# v0_5_1.net
KiCad netlist of a schematic drawn in EAGLE
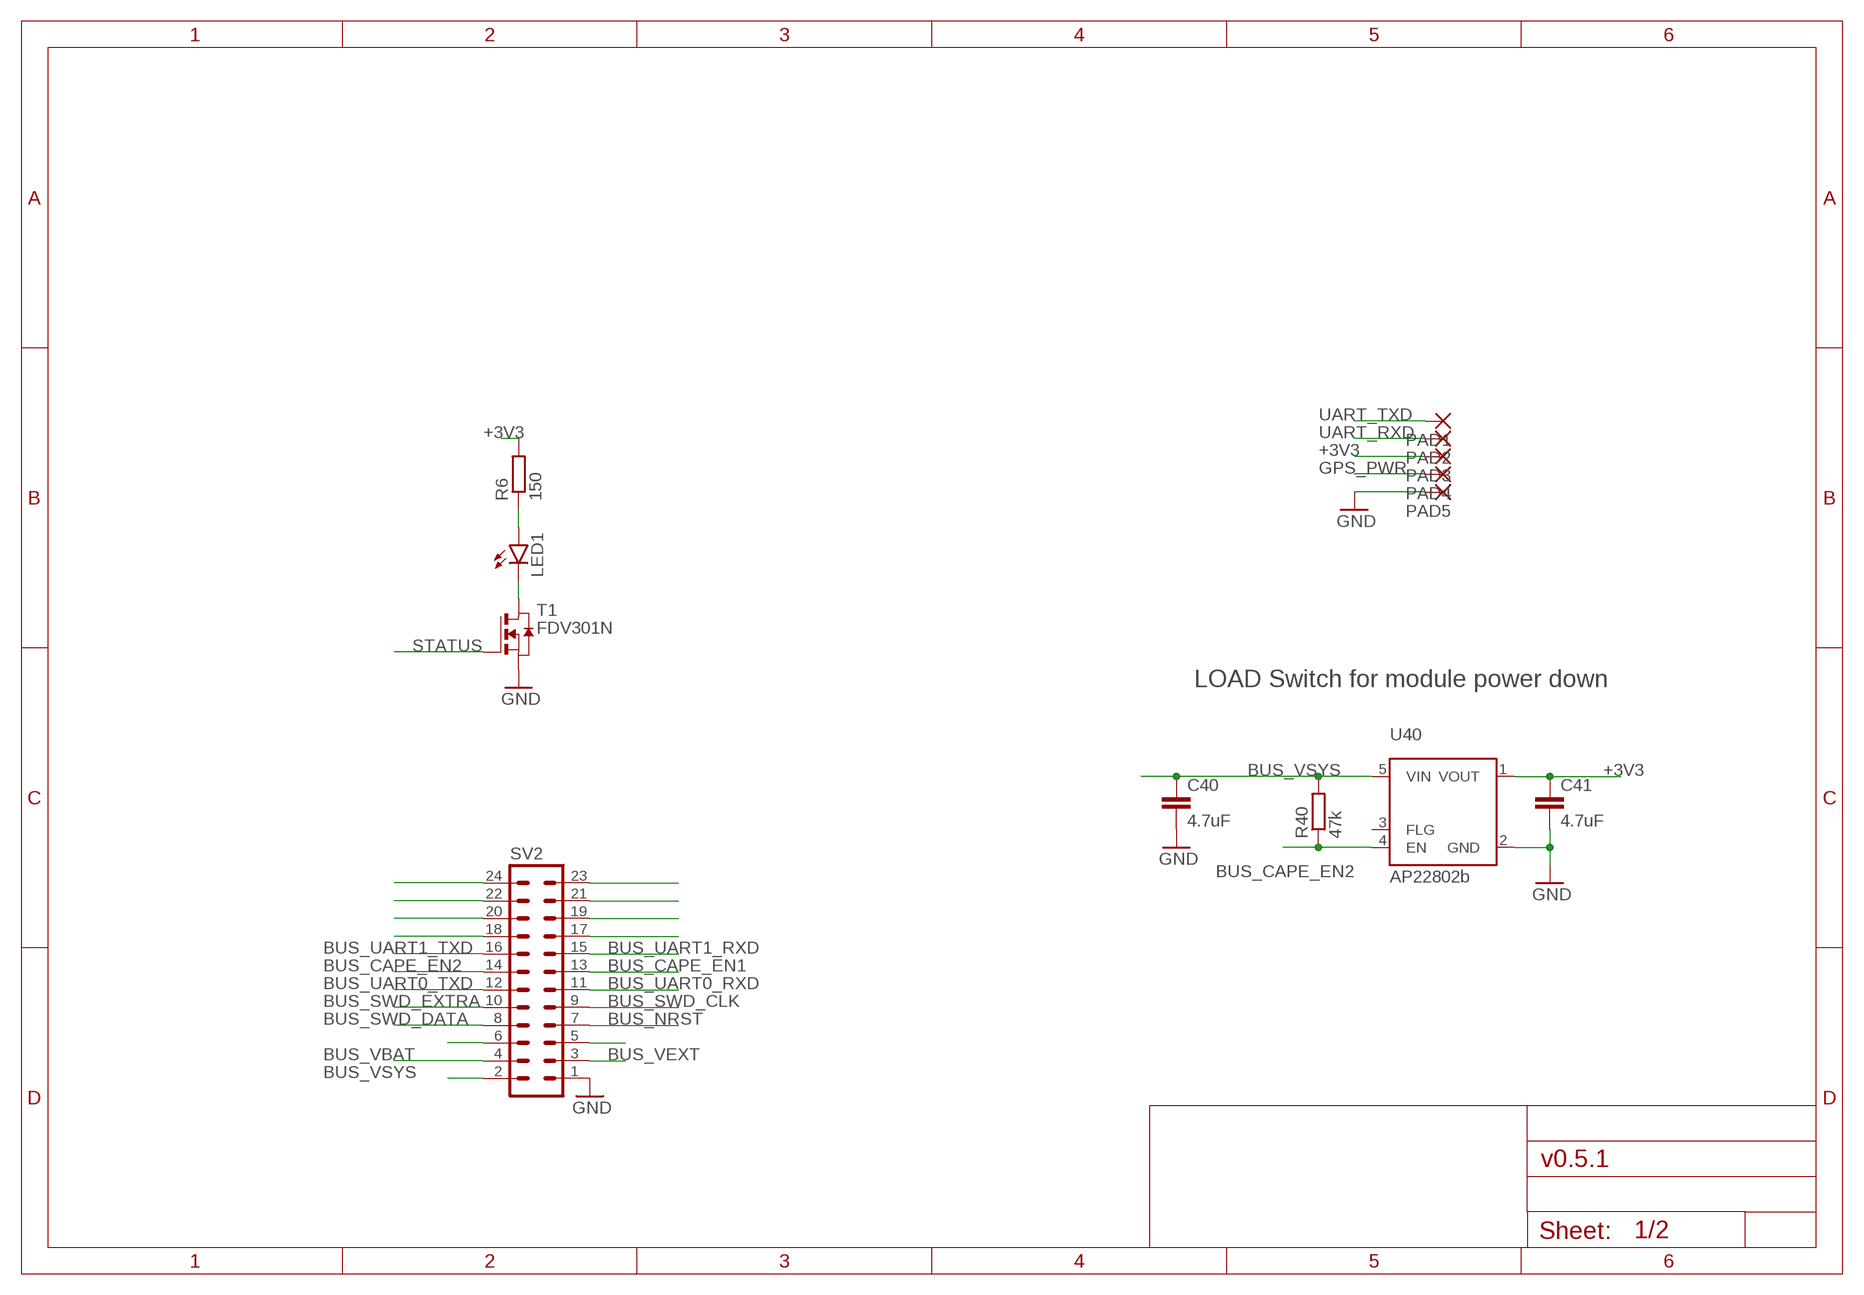
[diagram p0: schematic, sheet 1]
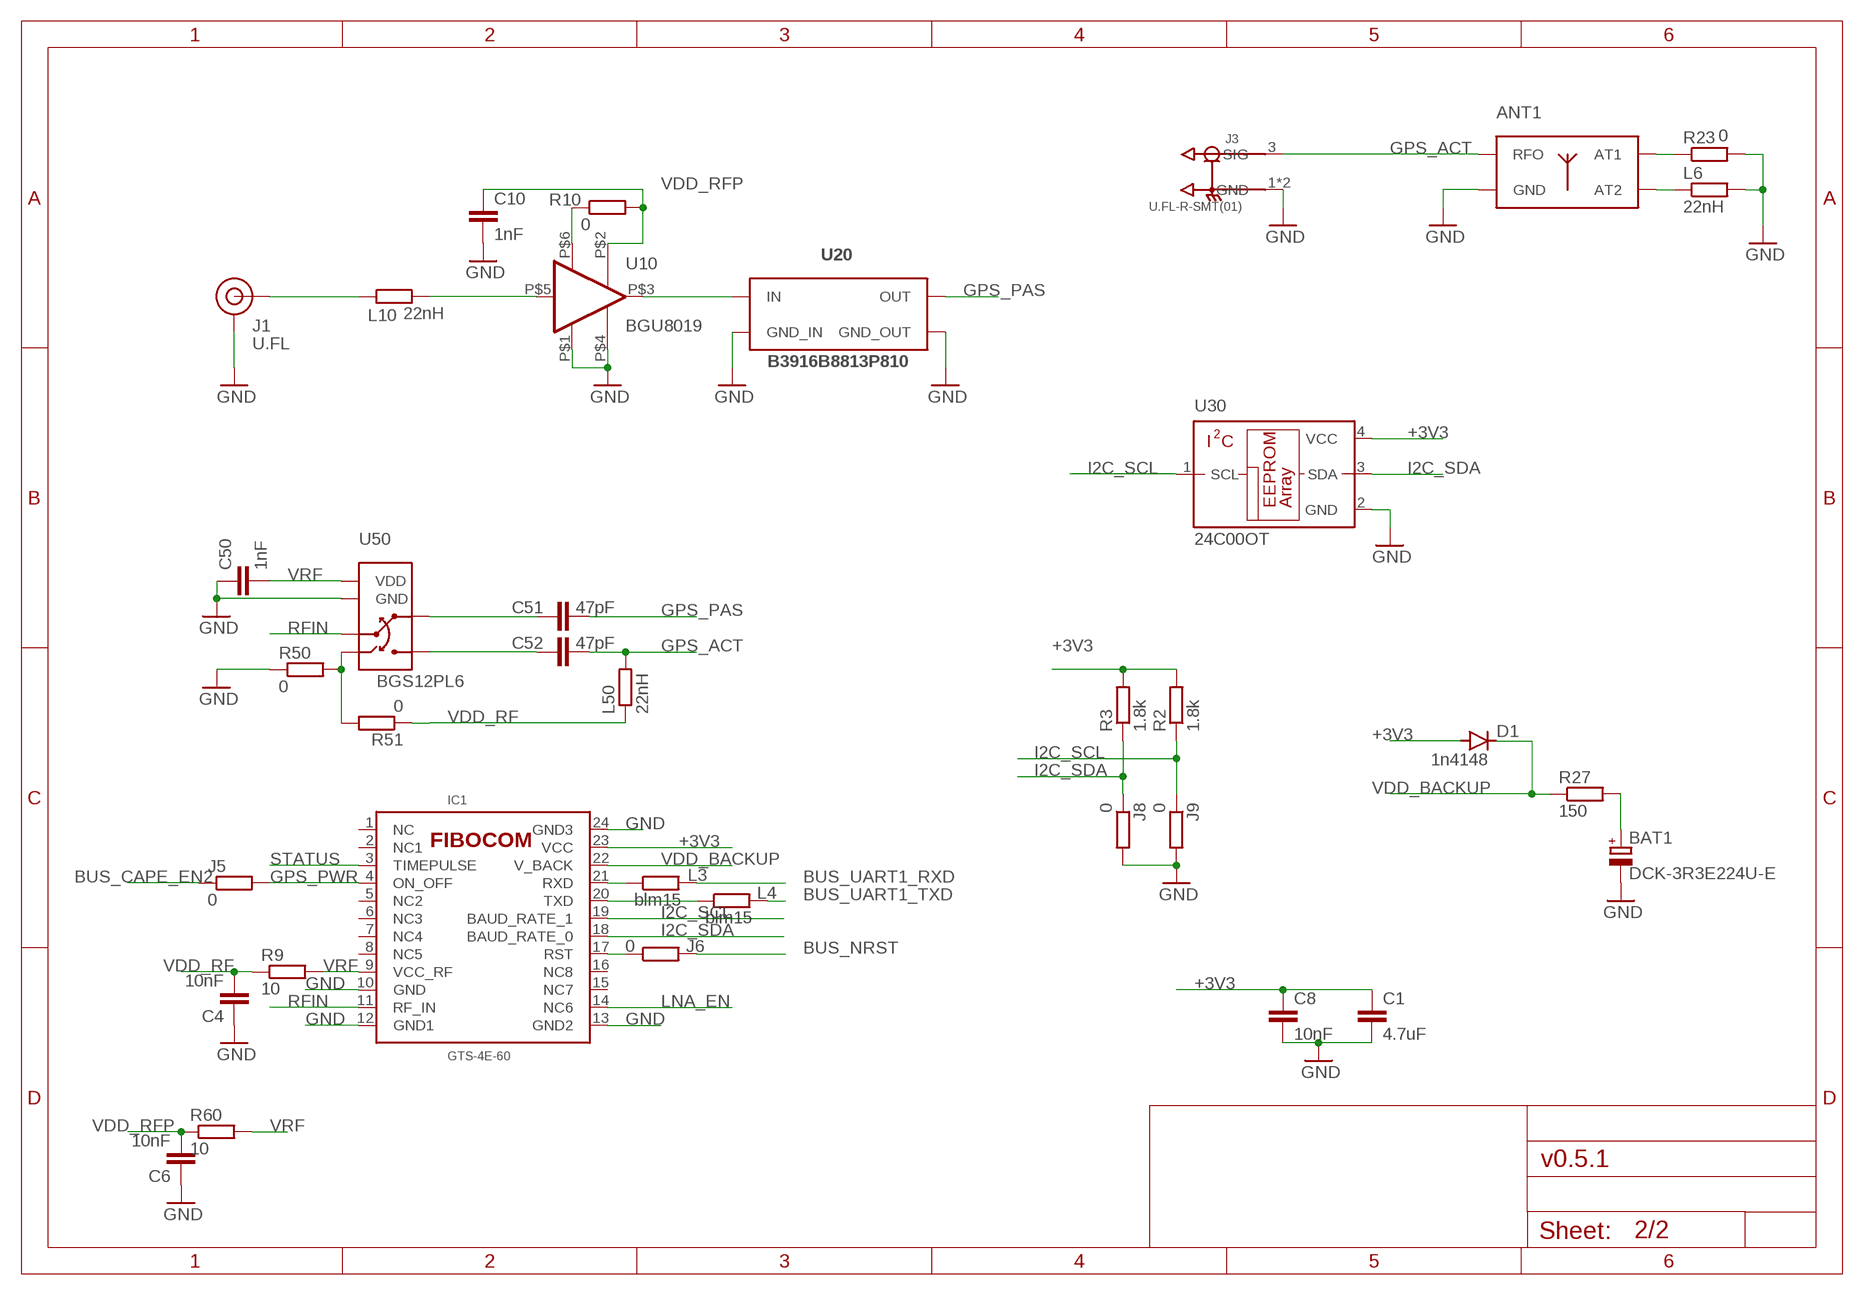
[diagram p1: schematic, sheet 2]

(export (version "E")
  (design (tool "Eeschema 10.0.6"))
  (components
    (comp (ref "C40")
      (value "4.7uF")
      (footprint "eagle-import:C0603")
      (libsource (lib "eagle-import") (part "C-EUC0603"))
    )
    (comp (ref "C41")
      (value "4.7uF")
      (footprint "eagle-import:C0603")
      (libsource (lib "eagle-import") (part "C-EUC0603"))
    )
    (comp (ref "LED1")
      (value "LEDCHIP-LED0603")
      (footprint "eagle-import:CHIP-LED0603")
      (libsource (lib "eagle-import") (part "LEDCHIP-LED0603"))
    )
    (comp (ref "PAD1")
      (value "1,6/0,9")
      (footprint "eagle-import:1,6_0,9")
      (libsource (lib "eagle-import") (part "1,6/0,9"))
    )
    (comp (ref "PAD2")
      (value "1,6/0,9")
      (footprint "eagle-import:1,6_0,9")
      (libsource (lib "eagle-import") (part "1,6/0,9"))
    )
    (comp (ref "PAD3")
      (value "1,6/0,9")
      (footprint "eagle-import:1,6_0,9")
      (libsource (lib "eagle-import") (part "1,6/0,9"))
    )
    (comp (ref "PAD4")
      (value "1,6/0,9")
      (footprint "eagle-import:1,6_0,9")
      (libsource (lib "eagle-import") (part "1,6/0,9"))
    )
    (comp (ref "PAD5")
      (value "1,6/0,9")
      (footprint "eagle-import:1,6_0,9")
      (libsource (lib "eagle-import") (part "1,6/0,9"))
    )
    (comp (ref "R6")
      (value "150")
      (footprint "eagle-import:R0402")
      (libsource (lib "eagle-import") (part "R-EU_R0402"))
    )
    (comp (ref "R40")
      (value "47k")
      (footprint "eagle-import:R0402")
      (libsource (lib "eagle-import") (part "R-EU_R0402"))
    )
    (comp (ref "SV2")
      (value "MA12-2")
      (footprint "eagle-import:MA12-2")
      (libsource (lib "eagle-import") (part "MA12-2"))
    )
    (comp (ref "T1")
      (value "FDV301N")
      (footprint "eagle-import:SOT-23")
      (libsource (lib "eagle-import") (part "NMOSSOT23"))
    )
    (comp (ref "U40")
      (value "AP22802b")
      (footprint "eagle-import:SOT25")
      (libsource (lib "eagle-import") (part "AP22802"))
    )
    (comp (ref "ANT1")
      (value "M20047")
      (footprint "eagle-import:PCBCOMPONENT_1")
      (libsource (lib "eagle-import") (part "M20047"))
    )
    (comp (ref "BAT1")
      (value "DCK-3R3E224U-E")
      (footprint "eagle-import:621")
      (libsource (lib "eagle-import") (part "DCK-3R3E224U-E"))
    )
    (comp (ref "C1")
      (value "4.7uF")
      (footprint "eagle-import:C0603")
      (libsource (lib "eagle-import") (part "C-EUC0603"))
    )
    (comp (ref "C4")
      (value "10nF")
      (footprint "eagle-import:C0402")
      (libsource (lib "eagle-import") (part "C-EUC0402"))
    )
    (comp (ref "C6")
      (value "10nF")
      (footprint "eagle-import:C0402")
      (libsource (lib "eagle-import") (part "C-EUC0402"))
    )
    (comp (ref "C8")
      (value "10nF")
      (footprint "eagle-import:C0402")
      (libsource (lib "eagle-import") (part "C-EUC0402"))
    )
    (comp (ref "C10")
      (value "1nF")
      (footprint "eagle-import:C0402")
      (libsource (lib "eagle-import") (part "C-EUC0402"))
    )
    (comp (ref "C50")
      (value "1nF")
      (footprint "eagle-import:C0402")
      (libsource (lib "eagle-import") (part "C-EUC0402"))
    )
    (comp (ref "C51")
      (value "47pF")
      (footprint "eagle-import:C0402")
      (libsource (lib "eagle-import") (part "C-EUC0402"))
    )
    (comp (ref "C52")
      (value "47pF")
      (footprint "eagle-import:C0402")
      (libsource (lib "eagle-import") (part "C-EUC0402"))
    )
    (comp (ref "D1")
      (value "1n4148")
      (footprint "eagle-import:SOD323-R")
      (libsource (lib "eagle-import") (part "DIODE-SOD323-R"))
    )
    (comp (ref "IC1")
      (value "GTS-4E-60")
      (footprint "eagle-import:_GTS_4E_60")
      (libsource (lib "eagle-import") (part "GTS-4E-60"))
    )
    (comp (ref "J1")
      (value "U.FL")
      (footprint "eagle-import:U.FL")
      (libsource (lib "eagle-import") (part "U.FL2PIN"))
    )
    (comp (ref "J3")
      (value "U.FL-R-SMT(01)")
      (footprint "eagle-import:HRS_U.FL-R-SMT(01)")
      (fields (field (name "MF") "Hirose") (field (name "MP") "U.FL-R-SMT_01_"))
      (libsource (lib "eagle-import") (part "U.FL-R-SMT(01)"))
    )
    (comp (ref "J5")
      (value "0")
      (footprint "eagle-import:R0402")
      (libsource (lib "eagle-import") (part "R-EU_R0402"))
    )
    (comp (ref "J6")
      (value "0")
      (footprint "eagle-import:R0402")
      (libsource (lib "eagle-import") (part "R-EU_R0402"))
    )
    (comp (ref "J8")
      (value "0")
      (footprint "eagle-import:R0402")
      (libsource (lib "eagle-import") (part "R-EU_R0402"))
    )
    (comp (ref "J9")
      (value "0")
      (footprint "eagle-import:R0402")
      (libsource (lib "eagle-import") (part "R-EU_R0402"))
    )
    (comp (ref "L3")
      (value "blm15")
      (footprint "eagle-import:R0402")
      (libsource (lib "eagle-import") (part "R-EU_R0402"))
    )
    (comp (ref "L4")
      (value "blm15")
      (footprint "eagle-import:R0402")
      (libsource (lib "eagle-import") (part "R-EU_R0402"))
    )
    (comp (ref "L6")
      (value "22nH")
      (footprint "eagle-import:R0402")
      (libsource (lib "eagle-import") (part "R-EU_R0402"))
    )
    (comp (ref "L10")
      (value "22nH")
      (footprint "eagle-import:R0402")
      (libsource (lib "eagle-import") (part "R-EU_R0402"))
    )
    (comp (ref "L50")
      (value "22nH")
      (footprint "eagle-import:R0402")
      (libsource (lib "eagle-import") (part "R-EU_R0402"))
    )
    (comp (ref "R2")
      (value "1.8k")
      (footprint "eagle-import:R0402")
      (libsource (lib "eagle-import") (part "R-EU_R0402"))
    )
    (comp (ref "R3")
      (value "1.8k")
      (footprint "eagle-import:R0402")
      (libsource (lib "eagle-import") (part "R-EU_R0402"))
    )
    (comp (ref "R9")
      (value "10")
      (footprint "eagle-import:R0402")
      (libsource (lib "eagle-import") (part "R-EU_R0402"))
    )
    (comp (ref "R10")
      (value "0")
      (footprint "eagle-import:R0402")
      (libsource (lib "eagle-import") (part "R-EU_R0402"))
    )
    (comp (ref "R23")
      (value "0")
      (footprint "eagle-import:R0402")
      (libsource (lib "eagle-import") (part "R-EU_R0402"))
    )
    (comp (ref "R27")
      (value "150")
      (footprint "eagle-import:R0402")
      (libsource (lib "eagle-import") (part "R-EU_R0402"))
    )
    (comp (ref "R50")
      (value "0")
      (footprint "eagle-import:R0402")
      (libsource (lib "eagle-import") (part "R-EU_R0402"))
    )
    (comp (ref "R51")
      (value "0")
      (footprint "eagle-import:R0402")
      (libsource (lib "eagle-import") (part "R-EU_R0402"))
    )
    (comp (ref "R60")
      (value "10")
      (footprint "eagle-import:R0402")
      (libsource (lib "eagle-import") (part "R-EU_R0402"))
    )
    (comp (ref "U10")
      (value "BGU8019")
      (footprint "eagle-import:XSON6")
      (libsource (lib "eagle-import") (part "BGU8019"))
    )
    (comp (ref "U20")
      (value "B3916B8813P810")
      (footprint "eagle-import:XSON5")
      (libsource (lib "eagle-import") (part "B3916B8813P810"))
    )
    (comp (ref "U30")
      (value "24C00OT")
      (footprint "eagle-import:SOT23-5L")
      (fields (field (name "MF") "MICROCHIP") (field (name "MPN") "24C00T-I/OT"))
      (libsource (lib "eagle-import") (part "2400OTC"))
    )
    (comp (ref "U50")
      (value "BGS12PL6")
      (footprint "eagle-import:TSLP-6-4")
      (libsource (lib "eagle-import") (part "BGS12PL6"))
    )
  )
  (nets
    (net (code "1") (name "+3V3") (class "Default")
      (node (ref "C1") (pin "1") (pinfunction "1_1") (pintype "passive"))
      (node (ref "C41") (pin "1") (pinfunction "1_1") (pintype "passive"))
      (node (ref "C8") (pin "1") (pinfunction "1_1") (pintype "passive"))
      (node (ref "D1") (pin "A") (pinfunction "A_A") (pintype "passive"))
      (node (ref "IC1") (pin "23") (pinfunction "VCC_23") (pintype "bidirectional"))
      (node (ref "PAD3") (pin "1") (pinfunction "P_1") (pintype "passive"))
      (node (ref "R2") (pin "2") (pinfunction "2_2") (pintype "passive"))
      (node (ref "R3") (pin "2") (pinfunction "2_2") (pintype "passive"))
      (node (ref "R6") (pin "2") (pinfunction "2_2") (pintype "passive"))
      (node (ref "U30") (pin "4") (pinfunction "VCC_4") (pintype "power_in"))
      (node (ref "U40") (pin "1") (pinfunction "VOUT_1") (pintype "bidirectional"))
    )
    (net (code "2") (name "BUS_CAPE_EN1") (class "Default")
      (node (ref "SV2") (pin "13") (pinfunction "13_13") (pintype "passive"))
    )
    (net (code "3") (name "BUS_CAPE_EN2") (class "Default")
      (node (ref "J5") (pin "1") (pinfunction "1_1") (pintype "passive"))
      (node (ref "R40") (pin "1") (pinfunction "1_1") (pintype "passive"))
      (node (ref "SV2") (pin "14") (pinfunction "14_14") (pintype "passive"))
      (node (ref "U40") (pin "4") (pinfunction "EN_4") (pintype "bidirectional"))
    )
    (net (code "4") (name "BUS_NRST") (class "Default")
      (node (ref "J6") (pin "2") (pinfunction "2_2") (pintype "passive"))
      (node (ref "SV2") (pin "7") (pinfunction "7_7") (pintype "passive"))
    )
    (net (code "5") (name "BUS_SWD_CLK") (class "Default")
      (node (ref "SV2") (pin "9") (pinfunction "9_9") (pintype "passive"))
    )
    (net (code "6") (name "BUS_SWD_DATA") (class "Default")
      (node (ref "SV2") (pin "8") (pinfunction "8_8") (pintype "passive"))
    )
    (net (code "7") (name "BUS_SWD_EXTRA") (class "Default")
      (node (ref "SV2") (pin "10") (pinfunction "10_10") (pintype "passive"))
    )
    (net (code "8") (name "BUS_UART0_RXD") (class "Default")
      (node (ref "SV2") (pin "11") (pinfunction "11_11") (pintype "passive"))
    )
    (net (code "9") (name "BUS_UART0_TXD") (class "Default")
      (node (ref "SV2") (pin "12") (pinfunction "12_12") (pintype "passive"))
    )
    (net (code "10") (name "BUS_UART1_RXD") (class "Default")
      (node (ref "L3") (pin "2") (pinfunction "2_2") (pintype "passive"))
      (node (ref "SV2") (pin "15") (pinfunction "15_15") (pintype "passive"))
    )
    (net (code "11") (name "BUS_UART1_TXD") (class "Default")
      (node (ref "L4") (pin "2") (pinfunction "2_2") (pintype "passive"))
      (node (ref "SV2") (pin "16") (pinfunction "16_16") (pintype "passive"))
    )
    (net (code "12") (name "BUS_VBAT") (class "Default")
      (node (ref "SV2") (pin "4") (pinfunction "4_4") (pintype "passive"))
    )
    (net (code "13") (name "BUS_VEXT") (class "Default")
      (node (ref "SV2") (pin "3") (pinfunction "3_3") (pintype "passive"))
    )
    (net (code "14") (name "BUS_VSYS") (class "Default")
      (node (ref "C40") (pin "1") (pinfunction "1_1") (pintype "passive"))
      (node (ref "R40") (pin "2") (pinfunction "2_2") (pintype "passive"))
      (node (ref "SV2") (pin "2") (pinfunction "2_2") (pintype "passive"))
      (node (ref "U40") (pin "5") (pinfunction "VIN_5") (pintype "bidirectional"))
    )
    (net (code "15") (name "GND") (class "Default")
      (node (ref "ANT1") (pin "2") (pinfunction "GND_2") (pintype "power_in"))
      (node (ref "ANT1") (pin "3") (pinfunction "GND_3") (pintype "power_in"))
      (node (ref "ANT1") (pin "4") (pinfunction "GND_4") (pintype "power_in"))
      (node (ref "BAT1") (pin "-") (pinfunction "-_-") (pintype "passive"))
      (node (ref "C1") (pin "2") (pinfunction "2_2") (pintype "passive"))
      (node (ref "C10") (pin "2") (pinfunction "2_2") (pintype "passive"))
      (node (ref "C4") (pin "1") (pinfunction "1_1") (pintype "passive"))
      (node (ref "C40") (pin "2") (pinfunction "2_2") (pintype "passive"))
      (node (ref "C41") (pin "2") (pinfunction "2_2") (pintype "passive"))
      (node (ref "C50") (pin "1") (pinfunction "1_1") (pintype "passive"))
      (node (ref "C6") (pin "1") (pinfunction "1_1") (pintype "passive"))
      (node (ref "C8") (pin "2") (pinfunction "2_2") (pintype "passive"))
      (node (ref "IC1") (pin "10") (pinfunction "GND_10") (pintype "bidirectional"))
      (node (ref "IC1") (pin "12") (pinfunction "GND1_12") (pintype "bidirectional"))
      (node (ref "IC1") (pin "13") (pinfunction "GND2_13") (pintype "bidirectional"))
      (node (ref "IC1") (pin "24") (pinfunction "GND3_24") (pintype "bidirectional"))
      (node (ref "J1") (pin "1") (pinfunction "GND_1") (pintype "bidirectional"))
      (node (ref "J1") (pin "2") (pinfunction "GND_2") (pintype "bidirectional"))
      (node (ref "J3") (pin "1") (pinfunction "GND_1") (pintype "passive"))
      (node (ref "J3") (pin "2") (pinfunction "GND_2") (pintype "passive"))
      (node (ref "J8") (pin "2") (pinfunction "2_2") (pintype "passive"))
      (node (ref "J9") (pin "2") (pinfunction "2_2") (pintype "passive"))
      (node (ref "L6") (pin "2") (pinfunction "2_2") (pintype "passive"))
      (node (ref "PAD5") (pin "1") (pinfunction "P_1") (pintype "passive"))
      (node (ref "R23") (pin "2") (pinfunction "2_2") (pintype "passive"))
      (node (ref "R50") (pin "1") (pinfunction "1_1") (pintype "passive"))
      (node (ref "SV2") (pin "1") (pinfunction "1_1") (pintype "passive"))
      (node (ref "T1") (pin "2") (pinfunction "S_2") (pintype "passive"))
      (node (ref "U10") (pin "P$1") (pinfunction "GND_P$1") (pintype "power_in"))
      (node (ref "U10") (pin "P$4") (pinfunction "GND_RF_P$4") (pintype "passive"))
      (node (ref "U20") (pin "2") (pinfunction "GND_IN_2") (pintype "bidirectional"))
      (node (ref "U20") (pin "3") (pinfunction "GND_OUT_3") (pintype "bidirectional"))
      (node (ref "U20") (pin "5") (pinfunction "GND_IN_5") (pintype "bidirectional"))
      (node (ref "U30") (pin "2") (pinfunction "GND_2") (pintype "power_in"))
      (node (ref "U40") (pin "2") (pinfunction "GND_2") (pintype "bidirectional"))
      (node (ref "U50") (pin "P$2") (pinfunction "GND_P$2") (pintype "power_in"))
    )
    (net (code "16") (name "GPS_ACT") (class "Default")
      (node (ref "ANT1") (pin "5") (pinfunction "RFO_5") (pintype "input"))
      (node (ref "C52") (pin "2") (pinfunction "2_2") (pintype "passive"))
      (node (ref "J3") (pin "3") (pinfunction "SIG_3") (pintype "passive"))
      (node (ref "L50") (pin "2") (pinfunction "2_2") (pintype "passive"))
    )
    (net (code "17") (name "GPS_PAS") (class "Default")
      (node (ref "C51") (pin "2") (pinfunction "2_2") (pintype "passive"))
      (node (ref "U20") (pin "4") (pinfunction "OUT_4") (pintype "bidirectional"))
    )
    (net (code "18") (name "GPS_PWR") (class "Default")
      (node (ref "IC1") (pin "4") (pinfunction "ON_OFF_4") (pintype "bidirectional"))
      (node (ref "J5") (pin "2") (pinfunction "2_2") (pintype "passive"))
      (node (ref "PAD4") (pin "1") (pinfunction "P_1") (pintype "passive"))
    )
    (net (code "19") (name "I2C_SCL") (class "Default")
      (node (ref "IC1") (pin "19") (pinfunction "BAUD_RATE_1_19") (pintype "bidirectional"))
      (node (ref "J9") (pin "1") (pinfunction "1_1") (pintype "passive"))
      (node (ref "R2") (pin "1") (pinfunction "1_1") (pintype "passive"))
      (node (ref "U30") (pin "1") (pinfunction "SCL_1") (pintype "input"))
    )
    (net (code "20") (name "I2C_SDA") (class "Default")
      (node (ref "IC1") (pin "18") (pinfunction "BAUD_RATE_0_18") (pintype "bidirectional"))
      (node (ref "J8") (pin "1") (pinfunction "1_1") (pintype "passive"))
      (node (ref "R3") (pin "1") (pinfunction "1_1") (pintype "passive"))
      (node (ref "U30") (pin "3") (pinfunction "SDA_3") (pintype "bidirectional"))
    )
    (net (code "21") (name "LNA_EN") (class "Default")
      (node (ref "IC1") (pin "14") (pinfunction "NC6_14") (pintype "bidirectional"))
    )
    (net (code "22") (name "Net-(ANT1-AT1)") (class "Default")
      (node (ref "ANT1") (pin "1") (pinfunction "AT1_1") (pintype "bidirectional"))
      (node (ref "R23") (pin "1") (pinfunction "1_1") (pintype "passive"))
    )
    (net (code "23") (name "Net-(ANT1-AT2)") (class "Default")
      (node (ref "ANT1") (pin "6") (pinfunction "AT2_6") (pintype "bidirectional"))
      (node (ref "L6") (pin "1") (pinfunction "1_1") (pintype "passive"))
    )
    (net (code "24") (name "Net-(BAT1-Pad+)") (class "Default")
      (node (ref "BAT1") (pin "+") (pinfunction "+_+") (pintype "passive"))
      (node (ref "R27") (pin "2") (pinfunction "2_2") (pintype "passive"))
    )
    (net (code "25") (name "Net-(IC1-RST)") (class "Default")
      (node (ref "IC1") (pin "17") (pinfunction "RST_17") (pintype "bidirectional"))
      (node (ref "J6") (pin "1") (pinfunction "1_1") (pintype "passive"))
    )
    (net (code "26") (name "Net-(J1-SIGNAL)") (class "Default")
      (node (ref "J1") (pin "FEED") (pinfunction "SIGNAL_FEED") (pintype "bidirectional"))
      (node (ref "L10") (pin "1") (pinfunction "1_1") (pintype "passive"))
    )
    (net (code "27") (name "Net-(LED1-PadA)") (class "Default")
      (node (ref "LED1") (pin "A") (pinfunction "A_A") (pintype "passive"))
      (node (ref "R6") (pin "1") (pinfunction "1_1") (pintype "passive"))
    )
    (net (code "28") (name "Net-(T1-D)") (class "Default")
      (node (ref "LED1") (pin "C") (pinfunction "C_C") (pintype "passive"))
      (node (ref "T1") (pin "1") (pinfunction "D_1") (pintype "passive"))
    )
    (net (code "29") (name "Net-(U10-ENABLE)") (class "Default")
      (node (ref "R10") (pin "1") (pinfunction "1_1") (pintype "passive"))
      (node (ref "U10") (pin "P$6") (pinfunction "ENABLE_P$6") (pintype "power_in"))
    )
    (net (code "30") (name "Net-(U10-RF_IN)") (class "Default")
      (node (ref "L10") (pin "2") (pinfunction "2_2") (pintype "passive"))
      (node (ref "U10") (pin "P$5") (pinfunction "RF_IN_P$5") (pintype "input"))
    )
    (net (code "31") (name "Net-(U10-RF_OUT)") (class "Default")
      (node (ref "U10") (pin "P$3") (pinfunction "RF_OUT_P$3") (pintype "output"))
      (node (ref "U20") (pin "1") (pinfunction "IN_1") (pintype "bidirectional"))
    )
    (net (code "32") (name "Net-(U50-P$4)") (class "Default")
      (node (ref "R50") (pin "2") (pinfunction "2_2") (pintype "passive"))
      (node (ref "R51") (pin "2") (pinfunction "2_2") (pintype "passive"))
      (node (ref "U50") (pin "P$6") (pinfunction "P$4_P$6") (pintype "bidirectional"))
    )
    (net (code "33") (name "Net-(U50-RF1)") (class "Default")
      (node (ref "C51") (pin "1") (pinfunction "1_1") (pintype "passive"))
      (node (ref "U50") (pin "P$3") (pinfunction "RF1_P$3") (pintype "bidirectional"))
    )
    (net (code "34") (name "Net-(U50-RF2)") (class "Default")
      (node (ref "C52") (pin "1") (pinfunction "1_1") (pintype "passive"))
      (node (ref "U50") (pin "P$1") (pinfunction "RF2_P$1") (pintype "bidirectional"))
    )
    (net (code "35") (name "RFIN") (class "Default")
      (node (ref "IC1") (pin "11") (pinfunction "RF_IN_11") (pintype "bidirectional"))
      (node (ref "U50") (pin "P$5") (pinfunction "RFIN_P$5") (pintype "bidirectional"))
    )
    (net (code "36") (name "STATUS") (class "Default")
      (node (ref "IC1") (pin "3") (pinfunction "TIMEPULSE_3") (pintype "bidirectional"))
      (node (ref "T1") (pin "3") (pinfunction "G_3") (pintype "passive"))
    )
    (net (code "37") (name "UART_RXD") (class "Default")
      (node (ref "IC1") (pin "20") (pinfunction "TXD_20") (pintype "bidirectional"))
      (node (ref "L4") (pin "1") (pinfunction "1_1") (pintype "passive"))
      (node (ref "PAD2") (pin "1") (pinfunction "P_1") (pintype "passive"))
    )
    (net (code "38") (name "UART_TXD") (class "Default")
      (node (ref "IC1") (pin "21") (pinfunction "RXD_21") (pintype "bidirectional"))
      (node (ref "L3") (pin "1") (pinfunction "1_1") (pintype "passive"))
      (node (ref "PAD1") (pin "1") (pinfunction "P_1") (pintype "passive"))
    )
    (net (code "39") (name "VDD_BACKUP") (class "Default")
      (node (ref "D1") (pin "C") (pinfunction "C_C") (pintype "passive"))
      (node (ref "IC1") (pin "22") (pinfunction "V_BACK_22") (pintype "bidirectional"))
      (node (ref "R27") (pin "1") (pinfunction "1_1") (pintype "passive"))
    )
    (net (code "40") (name "VDD_RF") (class "Default")
      (node (ref "C4") (pin "2") (pinfunction "2_2") (pintype "passive"))
      (node (ref "L50") (pin "1") (pinfunction "1_1") (pintype "passive"))
      (node (ref "R51") (pin "1") (pinfunction "1_1") (pintype "passive"))
      (node (ref "R9") (pin "1") (pinfunction "1_1") (pintype "passive"))
    )
    (net (code "41") (name "VDD_RFP") (class "Default")
      (node (ref "C10") (pin "1") (pinfunction "1_1") (pintype "passive"))
      (node (ref "C6") (pin "2") (pinfunction "2_2") (pintype "passive"))
      (node (ref "R10") (pin "2") (pinfunction "2_2") (pintype "passive"))
      (node (ref "R60") (pin "1") (pinfunction "1_1") (pintype "passive"))
      (node (ref "U10") (pin "P$2") (pinfunction "VCC_P$2") (pintype "passive"))
    )
    (net (code "42") (name "VRF") (class "Default")
      (node (ref "C50") (pin "2") (pinfunction "2_2") (pintype "passive"))
      (node (ref "IC1") (pin "9") (pinfunction "VCC_RF_9") (pintype "bidirectional"))
      (node (ref "R60") (pin "2") (pinfunction "2_2") (pintype "passive"))
      (node (ref "R9") (pin "2") (pinfunction "2_2") (pintype "passive"))
      (node (ref "U50") (pin "P$4") (pinfunction "VDD_P$4") (pintype "power_in"))
    )
    (net (code "43") (name "unconnected-(IC1-NC-Pad1)") (class "Default")
      (node (ref "IC1") (pin "1") (pinfunction "NC_1") (pintype "bidirectional"))
    )
    (net (code "44") (name "unconnected-(IC1-NC1-Pad2)") (class "Default")
      (node (ref "IC1") (pin "2") (pinfunction "NC1_2") (pintype "bidirectional"))
    )
    (net (code "45") (name "unconnected-(IC1-NC2-Pad5)") (class "Default")
      (node (ref "IC1") (pin "5") (pinfunction "NC2_5") (pintype "bidirectional"))
    )
    (net (code "46") (name "unconnected-(IC1-NC3-Pad6)") (class "Default")
      (node (ref "IC1") (pin "6") (pinfunction "NC3_6") (pintype "bidirectional"))
    )
    (net (code "47") (name "unconnected-(IC1-NC4-Pad7)") (class "Default")
      (node (ref "IC1") (pin "7") (pinfunction "NC4_7") (pintype "bidirectional"))
    )
    (net (code "48") (name "unconnected-(IC1-NC5-Pad8)") (class "Default")
      (node (ref "IC1") (pin "8") (pinfunction "NC5_8") (pintype "bidirectional"))
    )
    (net (code "49") (name "unconnected-(IC1-NC7-Pad15)") (class "Default")
      (node (ref "IC1") (pin "15") (pinfunction "NC7_15") (pintype "bidirectional"))
    )
    (net (code "50") (name "unconnected-(IC1-NC8-Pad16)") (class "Default")
      (node (ref "IC1") (pin "16") (pinfunction "NC8_16") (pintype "bidirectional"))
    )
    (net (code "51") (name "unconnected-(SV2-Pad5)") (class "Default")
      (node (ref "SV2") (pin "5") (pinfunction "5_5") (pintype "passive"))
    )
    (net (code "52") (name "unconnected-(SV2-Pad6)") (class "Default")
      (node (ref "SV2") (pin "6") (pinfunction "6_6") (pintype "passive"))
    )
    (net (code "53") (name "unconnected-(SV2-Pad17)") (class "Default")
      (node (ref "SV2") (pin "17") (pinfunction "17_17") (pintype "passive"))
    )
    (net (code "54") (name "unconnected-(SV2-Pad18)") (class "Default")
      (node (ref "SV2") (pin "18") (pinfunction "18_18") (pintype "passive"))
    )
    (net (code "55") (name "unconnected-(SV2-Pad19)") (class "Default")
      (node (ref "SV2") (pin "19") (pinfunction "19_19") (pintype "passive"))
    )
    (net (code "56") (name "unconnected-(SV2-Pad20)") (class "Default")
      (node (ref "SV2") (pin "20") (pinfunction "20_20") (pintype "passive"))
    )
    (net (code "57") (name "unconnected-(SV2-Pad21)") (class "Default")
      (node (ref "SV2") (pin "21") (pinfunction "21_21") (pintype "passive"))
    )
    (net (code "58") (name "unconnected-(SV2-Pad22)") (class "Default")
      (node (ref "SV2") (pin "22") (pinfunction "22_22") (pintype "passive"))
    )
    (net (code "59") (name "unconnected-(SV2-Pad23)") (class "Default")
      (node (ref "SV2") (pin "23") (pinfunction "23_23") (pintype "passive"))
    )
    (net (code "60") (name "unconnected-(SV2-Pad24)") (class "Default")
      (node (ref "SV2") (pin "24") (pinfunction "24_24") (pintype "passive"))
    )
    (net (code "61") (name "unconnected-(U40-FLG-Pad3)") (class "Default")
      (node (ref "U40") (pin "3") (pinfunction "FLG_3") (pintype "bidirectional"))
    )
  )
)
